# esc.net
KiCad netlist of a schematic drawn in EasyEDA Pro
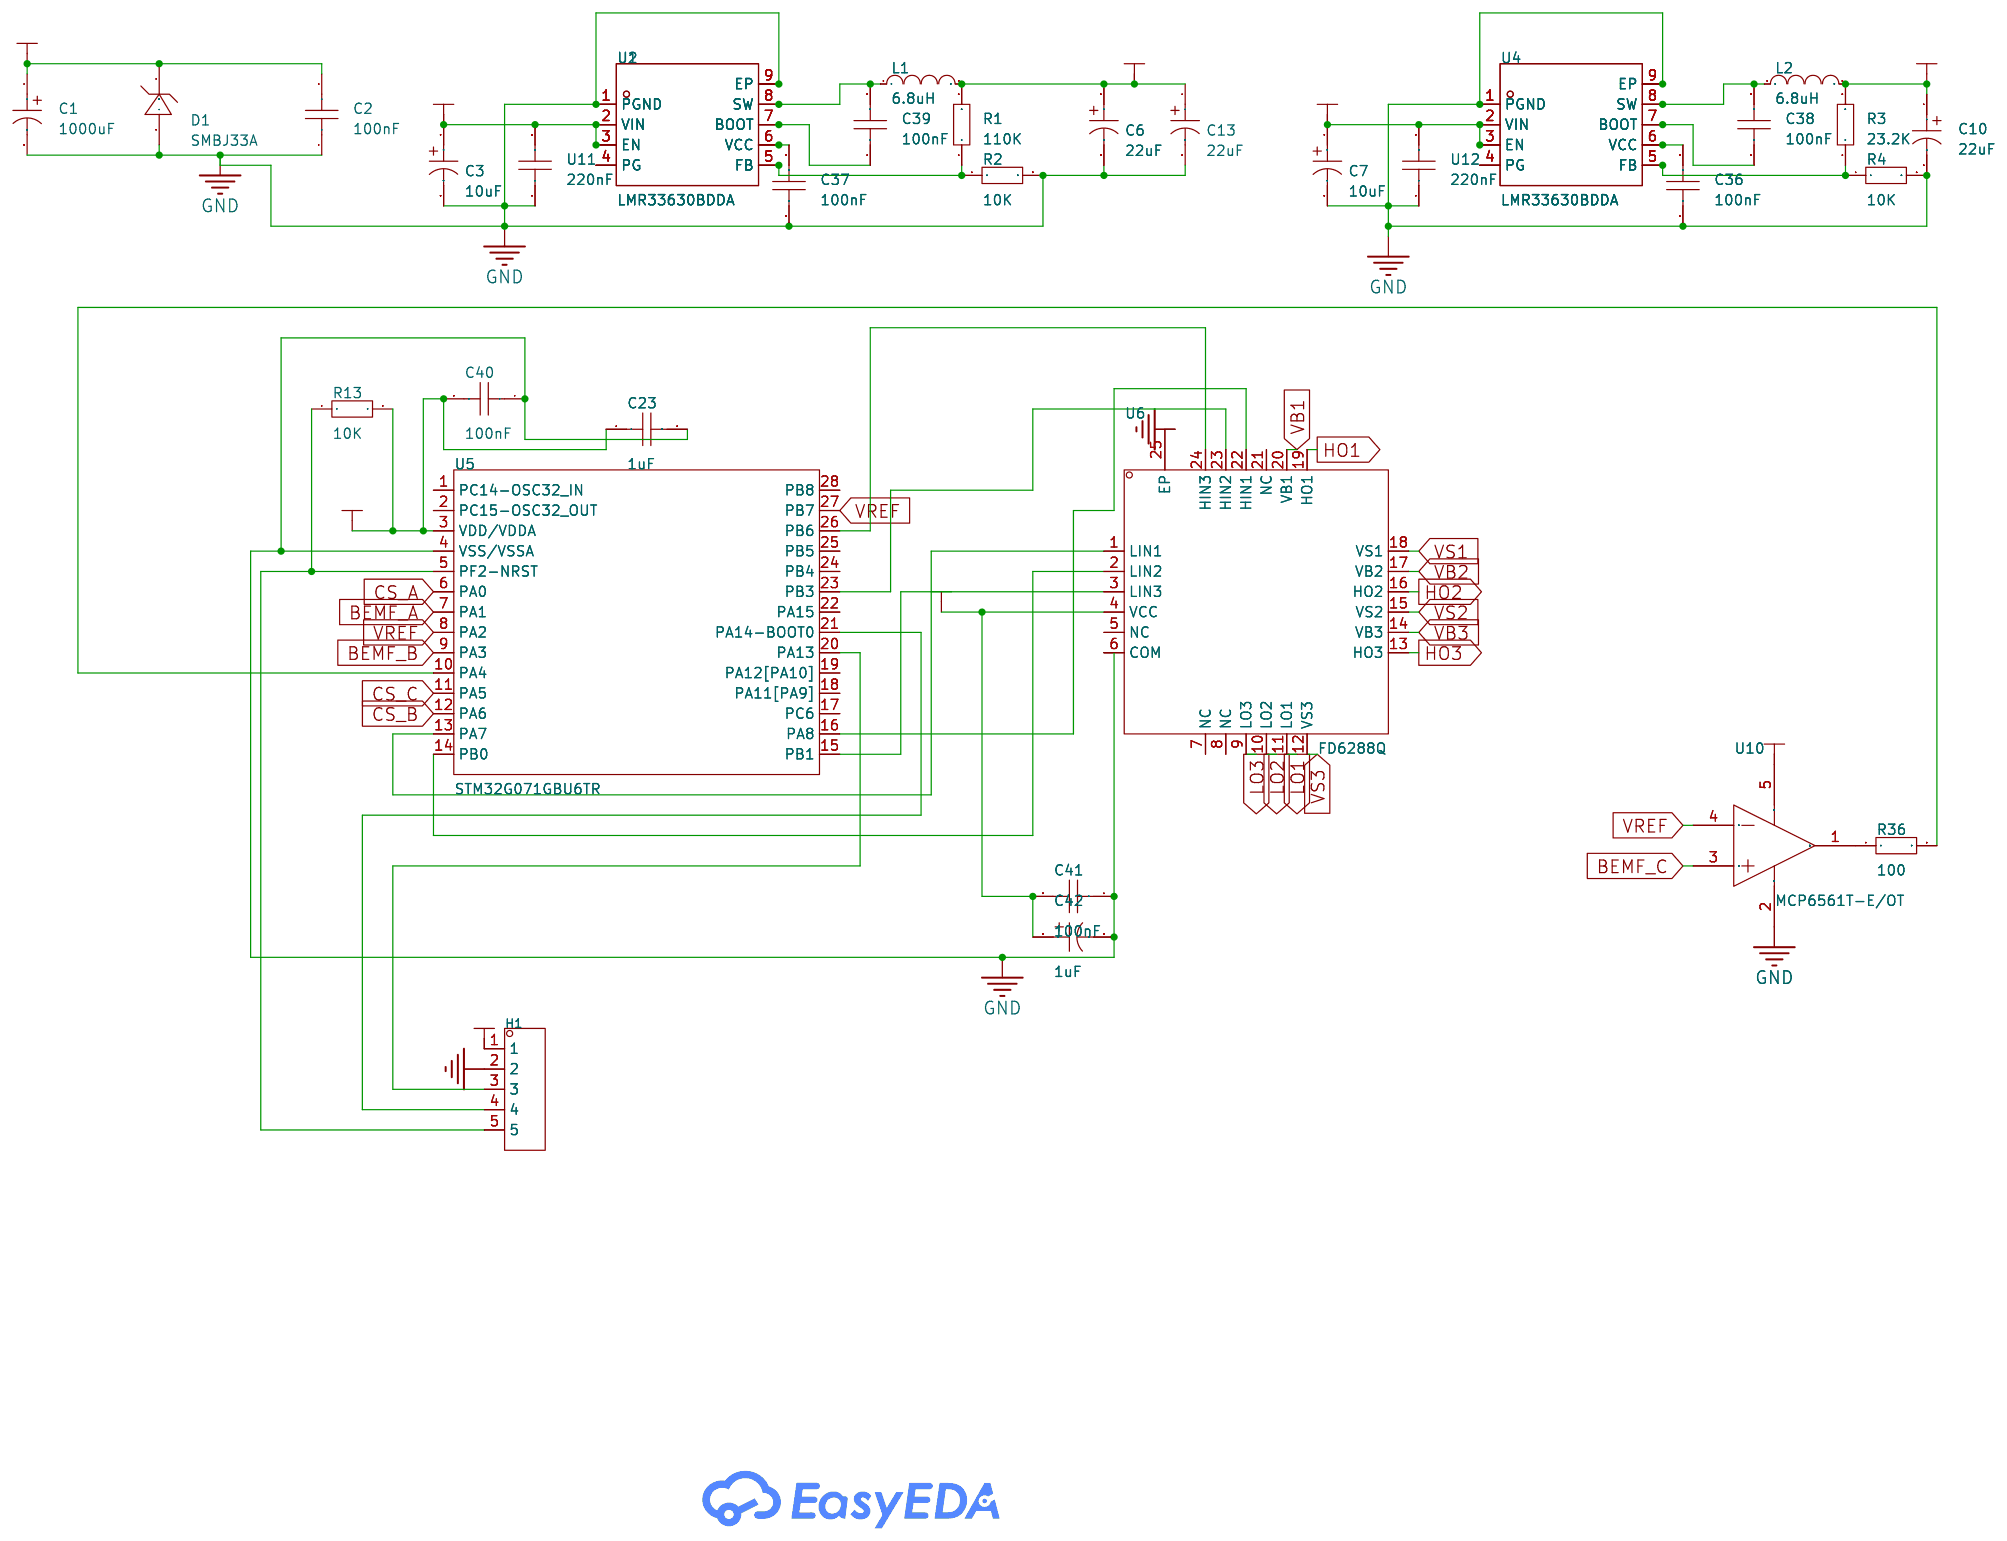
[diagram p0: P1]
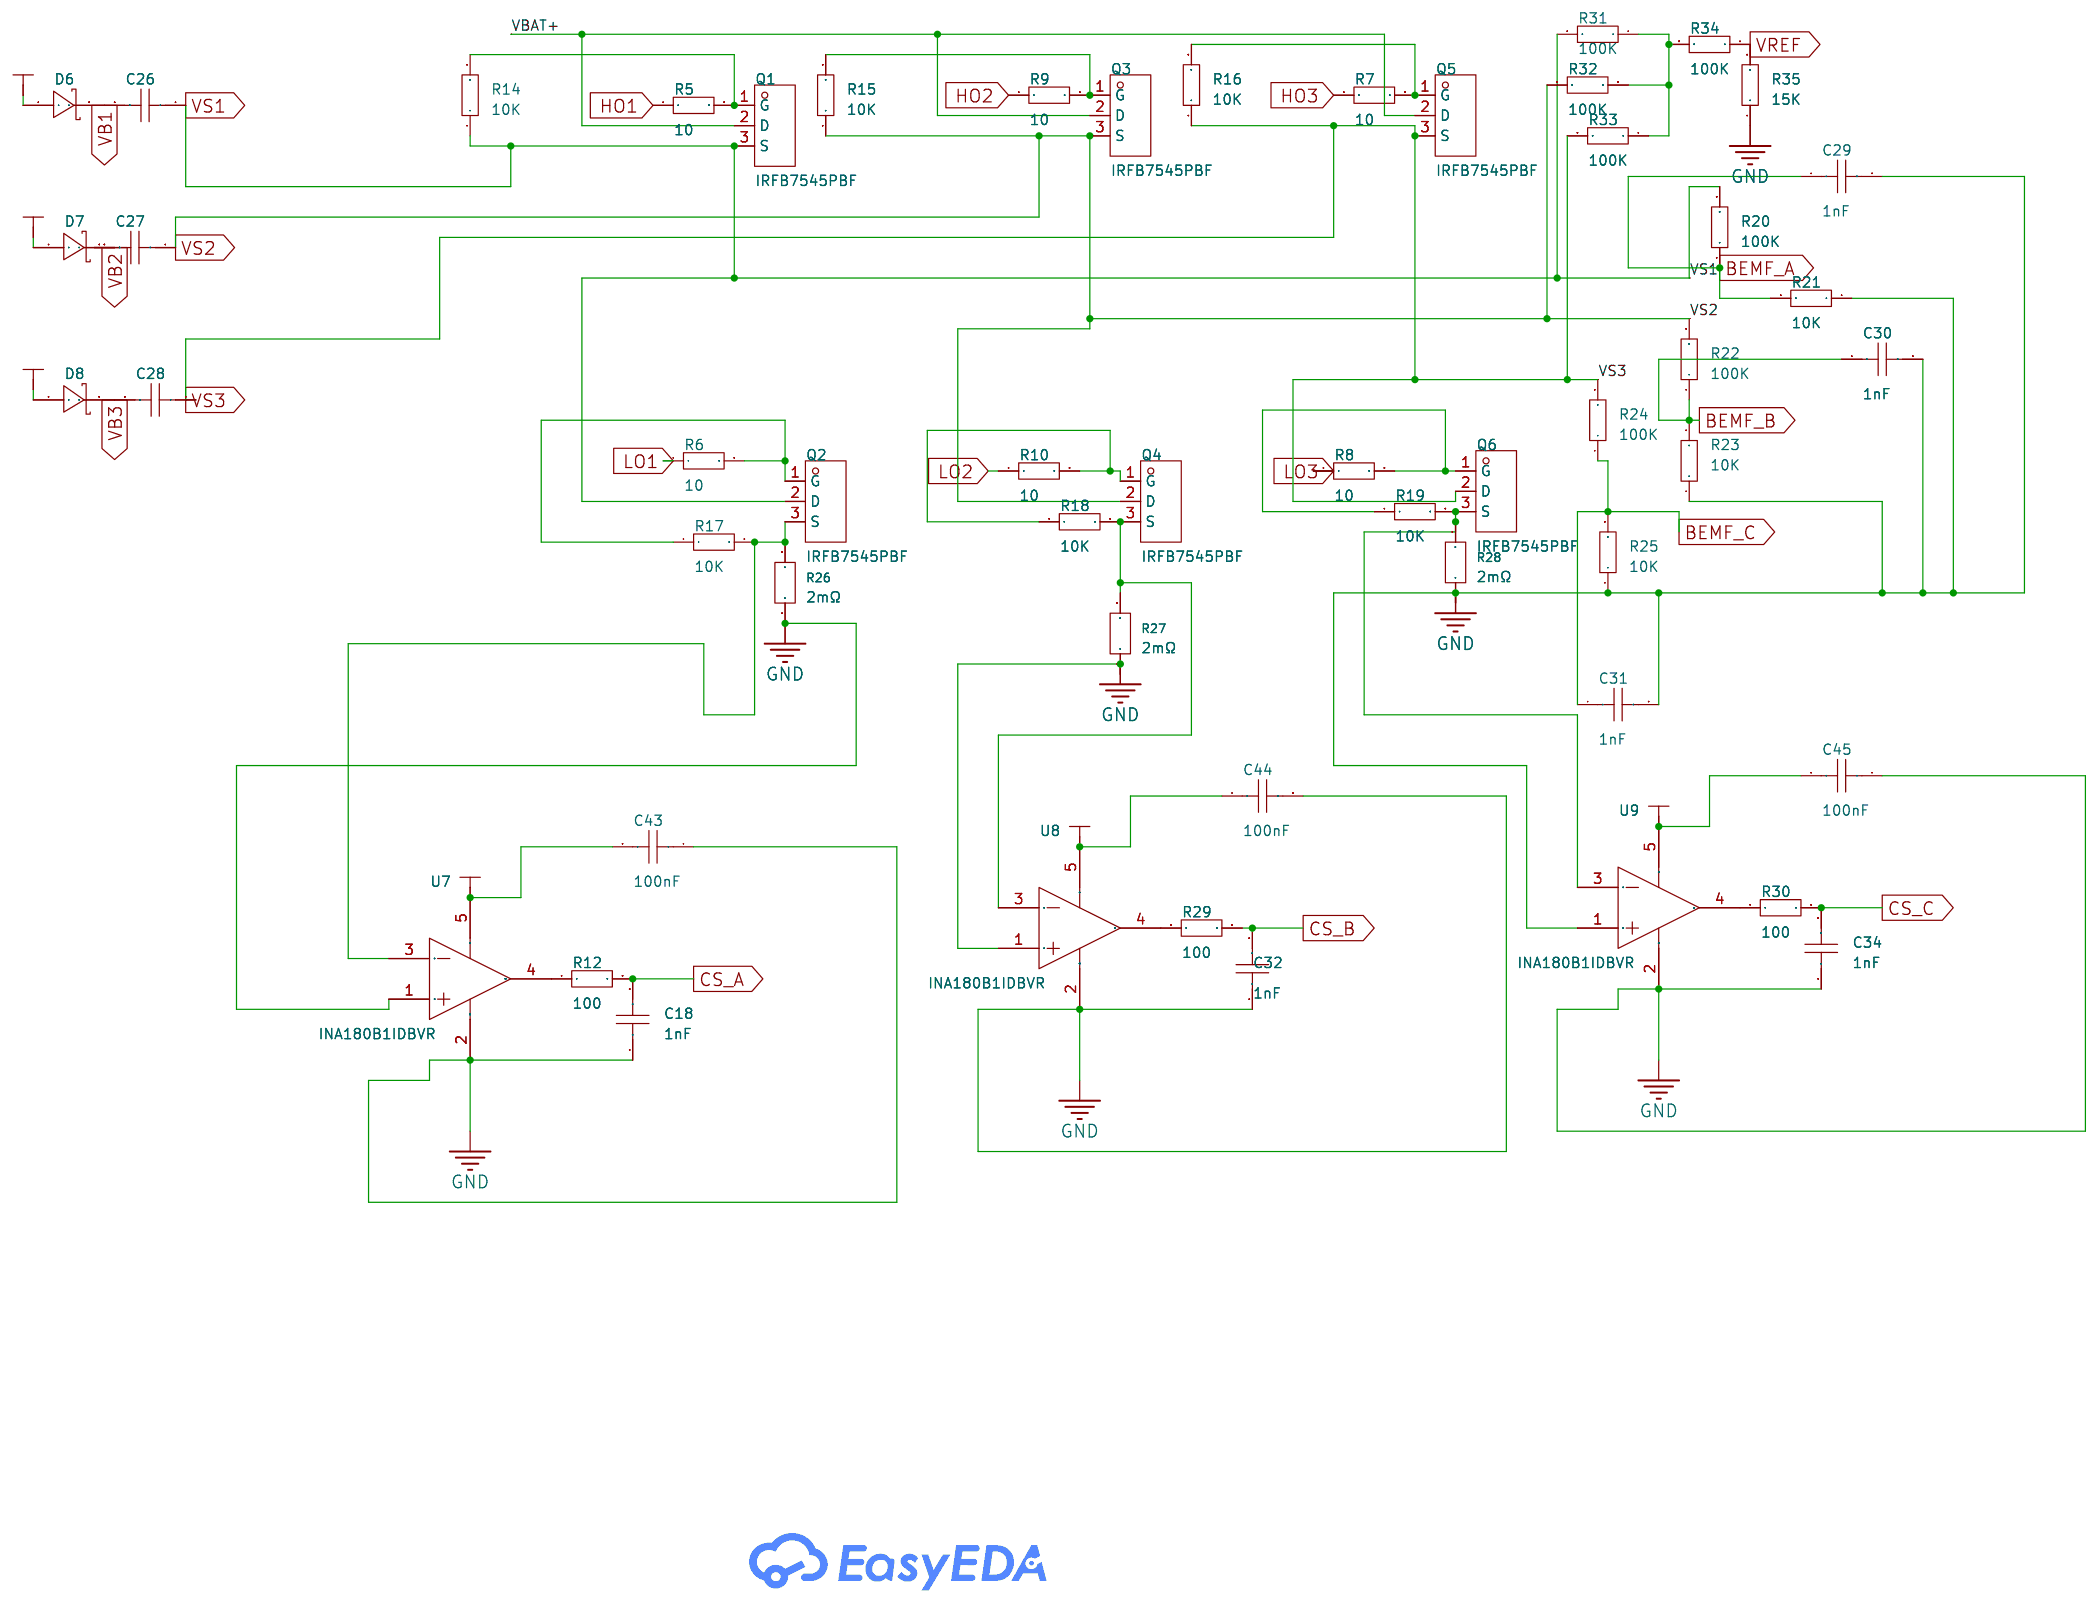
[diagram p1: P2]

(export (version "E")
  (design (tool "Eeschema 10.0.6"))
  (components
    (comp (ref "C1")
      (value "1000uF")
      (footprint "easyedapro:CAP-TH_BD13.0-P5.00-D0.6-FD")
      (fields (field (name "Manufacturer Part") "50V1000uF CD288") (field (name "Manufacturer") "HRK(鸿瑞凯电子)"))
      (libsource (lib "easyedapro") (part "50V1000UF CD288"))
    )
    (comp (ref "C2")
      (value "100nF")
      (footprint "easyedapro:C1111")
      (fields
        (field (name "Manufacturer Part") "200B104MT50XT1K")
        (field (name "Manufacturer") "Kyocera AVX")
      )
      (libsource (lib "easyedapro") (part "200B104MT50XT1K"))
    )
    (comp (ref "C3")
      (value "10uF")
      (footprint "easyedapro:CAP-TH_BD5.0-P2.00-D0.5-FD-1")
      (fields (field (name "Manufacturer Part") "50V10uF CD110") (field (name "Manufacturer") "HRK(鸿瑞凯电子)"))
      (libsource (lib "easyedapro") (part "50V10UF CD110_C2960373"))
    )
    (comp (ref "C6")
      (value "22uF")
      (footprint "easyedapro:CAP-TH_BD5.0-P2.00-D0.5-FD-1")
      (fields (field (name "Manufacturer Part") "22UF50VC110GF") (field (name "Manufacturer") "Econd(米朗电子)"))
      (libsource (lib "easyedapro") (part "22UF50VC110GF"))
    )
    (comp (ref "C7")
      (value "10uF")
      (footprint "easyedapro:CAP-TH_BD5.0-P2.00-D0.5-FD-1")
      (fields (field (name "Manufacturer Part") "50V10uF CD110") (field (name "Manufacturer") "HRK(鸿瑞凯电子)"))
      (libsource (lib "easyedapro") (part "50V10UF CD110_C2960373"))
    )
    (comp (ref "C10")
      (value "22uF")
      (footprint "easyedapro:CAP-TH_BD5.0-P2.00-D0.5-FD-1")
      (fields (field (name "Manufacturer Part") "22UF50VC110GF") (field (name "Manufacturer") "Econd(米朗电子)"))
      (libsource (lib "easyedapro") (part "22UF50VC110GF"))
    )
    (comp (ref "C13")
      (value "22uF")
      (footprint "easyedapro:CAP-TH_BD5.0-P2.00-D0.5-FD-1")
      (fields (field (name "Manufacturer Part") "22UF50VC110GF") (field (name "Manufacturer") "Econd(米朗电子)"))
      (libsource (lib "easyedapro") (part "22UF50VC110GF"))
    )
    (comp (ref "C23")
      (value "1uF")
      (footprint "easyedapro:C0603")
      (libsource (lib "easyedapro") (part "CapAcitance"))
    )
    (comp (ref "C36")
      (value "100nF")
      (footprint "easyedapro:C0603")
      (description "Capacitance:100nF Voltage Rating:50V Temperature Coefficient:X7R")
      (fields
        (field (name "Manufacturer Part") "CS1608X7R104K500NRB")
        (field (name "Manufacturer") "SAMWHA(三和)")
      )
      (libsource (lib "easyedapro") (part "CS1608X7R104K500NRB"))
    )
    (comp (ref "C37")
      (value "100nF")
      (footprint "easyedapro:C0603")
      (description "Capacitance:100nF Voltage Rating:50V Temperature Coefficient:X7R")
      (fields
        (field (name "Manufacturer Part") "CS1608X7R104K500NRB")
        (field (name "Manufacturer") "SAMWHA(三和)")
      )
      (libsource (lib "easyedapro") (part "CS1608X7R104K500NRB"))
    )
    (comp (ref "C38")
      (value "100nF")
      (footprint "easyedapro:C0603")
      (description "Capacitance:100nF Voltage Rating:50V Temperature Coefficient:X7R")
      (fields
        (field (name "Manufacturer Part") "CS1608X7R104K500NRB")
        (field (name "Manufacturer") "SAMWHA(三和)")
      )
      (libsource (lib "easyedapro") (part "CS1608X7R104K500NRB"))
    )
    (comp (ref "C39")
      (value "100nF")
      (footprint "easyedapro:C0603")
      (description "Capacitance:100nF Voltage Rating:50V Temperature Coefficient:X7R")
      (fields
        (field (name "Manufacturer Part") "CS1608X7R104K500NRB")
        (field (name "Manufacturer") "SAMWHA(三和)")
      )
      (libsource (lib "easyedapro") (part "CS1608X7R104K500NRB"))
    )
    (comp (ref "C40")
      (value "100nF")
      (footprint "easyedapro:C0603")
      (description "Capacitance:100nF Voltage Rating:50V Temperature Coefficient:X7R")
      (fields
        (field (name "Manufacturer Part") "CS1608X7R104K500NRB")
        (field (name "Manufacturer") "SAMWHA(三和)")
      )
      (libsource (lib "easyedapro") (part "CS1608X7R104K500NRB"))
    )
    (comp (ref "C41")
      (value "100nF")
      (footprint "easyedapro:C0603")
      (description "Capacitance:100nF Voltage Rating:50V Temperature Coefficient:X7R")
      (fields
        (field (name "Manufacturer Part") "CS1608X7R104K500NRB")
        (field (name "Manufacturer") "SAMWHA(三和)")
      )
      (libsource (lib "easyedapro") (part "CS1608X7R104K500NRB"))
    )
    (comp (ref "C42")
      (value "1uF")
      (footprint "easyedapro:CAP-TH_BD5.0-P2.00-D0.5-FD_1UF50V5X11GF")
      (fields (field (name "Manufacturer Part") "1uF50V5x11GF") (field (name "Manufacturer") "Econd(米朗电子)"))
      (libsource (lib "easyedapro") (part "1UF50V5X11GF"))
    )
    (comp (ref "D1")
      (value "SMBJ33A")
      (footprint "easyedapro:SMB_L4.6-W3.7-LS5.4-RD")
      (fields (field (name "Manufacturer") "PDW(芯格诺科技)"))
      (libsource (lib "easyedapro") (part "SMBJ33A_C49242950"))
    )
    (comp (ref "H1")
      (value "~")
      (footprint "easyedapro:HDR-TH_5P-P2.54-V-M")
      (libsource (lib "easyedapro") (part "MTP125-1105S1"))
    )
    (comp (ref "L1")
      (value "6.8uH")
      (footprint "easyedapro:L0603")
      (libsource (lib "easyedapro") (part "电感"))
    )
    (comp (ref "L2")
      (value "6.8uH")
      (footprint "easyedapro:L0603")
      (libsource (lib "easyedapro") (part "电感"))
    )
    (comp (ref "R1")
      (value "110K")
      (footprint "easyedapro:R0603")
      (libsource (lib "easyedapro") (part "Res"))
    )
    (comp (ref "R2") (value "10K") (footprint "easyedapro:R0603") (libsource (lib "easyedapro") (part "Res")))
    (comp (ref "R3")
      (value "23.2K")
      (footprint "easyedapro:R0603")
      (libsource (lib "easyedapro") (part "Res"))
    )
    (comp (ref "R4") (value "10K") (footprint "easyedapro:R0603") (libsource (lib "easyedapro") (part "Res")))
    (comp (ref "R13") (value "10K") (footprint "easyedapro:R0603") (libsource (lib "easyedapro") (part "电阻")))
    (comp (ref "R36")
      (value "100")
      (footprint "easyedapro:R0603")
      (libsource (lib "easyedapro") (part "Res"))
    )
    (comp (ref "U1")
      (value "LMR33630BDDA")
      (footprint "easyedapro:POWERPAD-SO-8_L4.9-W3.9-P1.27-LS6.0-BL-EP")
      (fields (field (name "Manufacturer") "TI(德州仪器)"))
      (libsource (lib "easyedapro") (part "LMR33630BDDA"))
    )
    (comp (ref "U2")
      (value "LMR33630BDDA")
      (footprint "easyedapro:POWERPAD-SO-8_L4.9-W3.9-P1.27-LS6.0-BL-EP")
      (fields (field (name "Manufacturer") "TI(德州仪器)"))
      (libsource (lib "easyedapro") (part "LMR33630BDDA"))
    )
    (comp (ref "U3")
      (value "LMR33630BDDA")
      (footprint "easyedapro:POWERPAD-SO-8_L4.9-W3.9-P1.27-LS6.0-BL-EP")
      (fields (field (name "Manufacturer") "TI(德州仪器)"))
      (libsource (lib "easyedapro") (part "LMR33630BDDA"))
    )
    (comp (ref "U4")
      (value "LMR33630BDDA")
      (footprint "easyedapro:POWERPAD-SO-8_L4.9-W3.9-P1.27-LS6.0-BL-EP")
      (fields (field (name "Manufacturer") "TI(德州仪器)"))
      (libsource (lib "easyedapro") (part "LMR33630BDDA"))
    )
    (comp (ref "U5")
      (value "STM32G071GBU6TR")
      (footprint "easyedapro:UFQFPN-28_L4.0-W4.0-P0.50-BL")
      (fields (field (name "Manufacturer") "ST(意法半导体)"))
      (libsource (lib "easyedapro") (part "STM32G071GBU6TR"))
    )
    (comp (ref "U6")
      (value "FD6288Q")
      (footprint "easyedapro:QFN-24_L4.0-W4.0-P0.50-BL-EP2.6")
      (fields (field (name "Manufacturer") "Fortior Tech(峰岹)"))
      (libsource (lib "easyedapro") (part "FD6288Q_C328453"))
    )
    (comp (ref "U10")
      (value "MCP6561T-E/OT")
      (footprint "easyedapro:SOT-23-5_L3.0-W1.7-P0.95-LS2.8-BR")
      (fields (field (name "Manufacturer") "MICROCHIP(美国微芯)"))
      (libsource (lib "easyedapro") (part "MCP6561T-E/OT"))
    )
    (comp (ref "U11")
      (value "220nF")
      (footprint "easyedapro:CAP-TH_L4.0-W2.5-P2.50-D0.5")
      (description "Capacitance:220nF Tolerance:±10% Tolerance:±10% Voltage Rating:50V Temperature Coefficient:X7R")
      (fields (field (name "Manufacturer Part") "FK18X7R1H224K") (field (name "Manufacturer") "TDK"))
      (libsource (lib "easyedapro") (part "FK18X7R1H224K"))
    )
    (comp (ref "U12")
      (value "220nF")
      (footprint "easyedapro:CAP-TH_L4.0-W2.5-P2.50-D0.5")
      (description "Capacitance:220nF Tolerance:±10% Tolerance:±10% Voltage Rating:50V Temperature Coefficient:X7R")
      (fields (field (name "Manufacturer Part") "FK18X7R1H224K") (field (name "Manufacturer") "TDK"))
      (libsource (lib "easyedapro") (part "FK18X7R1H224K"))
    )
    (comp (ref "C18")
      (value "1nF")
      (footprint "easyedapro:C0603")
      (libsource (lib "easyedapro") (part "CAP"))
    )
    (comp (ref "C26")
      (value "220nF")
      (footprint "easyedapro:C0805")
      (fields
        (field (name "Manufacturer Part") "TCC0805X7R224K500DT")
        (field (name "Manufacturer") "CCTC(三环)")
      )
      (libsource (lib "easyedapro") (part "TCC0805X7R224K500DT"))
    )
    (comp (ref "C27")
      (value "220nF")
      (footprint "easyedapro:C0805")
      (fields
        (field (name "Manufacturer Part") "TCC0805X7R224K500DT")
        (field (name "Manufacturer") "CCTC(三环)")
      )
      (libsource (lib "easyedapro") (part "TCC0805X7R224K500DT"))
    )
    (comp (ref "C28")
      (value "220nF")
      (footprint "easyedapro:C0805")
      (fields
        (field (name "Manufacturer Part") "TCC0805X7R224K500DT")
        (field (name "Manufacturer") "CCTC(三环)")
      )
      (libsource (lib "easyedapro") (part "TCC0805X7R224K500DT"))
    )
    (comp (ref "C29")
      (value "1nF")
      (footprint "easyedapro:C0603")
      (libsource (lib "easyedapro") (part "CapAcitance"))
    )
    (comp (ref "C30")
      (value "1nF")
      (footprint "easyedapro:C0603")
      (libsource (lib "easyedapro") (part "CapAcitance"))
    )
    (comp (ref "C31")
      (value "1nF")
      (footprint "easyedapro:C0603")
      (libsource (lib "easyedapro") (part "CapAcitance"))
    )
    (comp (ref "C32")
      (value "1nF")
      (footprint "easyedapro:C0603")
      (libsource (lib "easyedapro") (part "CAP"))
    )
    (comp (ref "C34")
      (value "1nF")
      (footprint "easyedapro:C0603")
      (libsource (lib "easyedapro") (part "CAP"))
    )
    (comp (ref "C43")
      (value "100nF")
      (footprint "easyedapro:C0603")
      (description "Capacitance:100nF Voltage Rating:50V Temperature Coefficient:X7R")
      (fields
        (field (name "Manufacturer Part") "CS1608X7R104K500NRB")
        (field (name "Manufacturer") "SAMWHA(三和)")
      )
      (libsource (lib "easyedapro") (part "CS1608X7R104K500NRB"))
    )
    (comp (ref "C44")
      (value "100nF")
      (footprint "easyedapro:C0603")
      (description "Capacitance:100nF Voltage Rating:50V Temperature Coefficient:X7R")
      (fields
        (field (name "Manufacturer Part") "CS1608X7R104K500NRB")
        (field (name "Manufacturer") "SAMWHA(三和)")
      )
      (libsource (lib "easyedapro") (part "CS1608X7R104K500NRB"))
    )
    (comp (ref "C45")
      (value "100nF")
      (footprint "easyedapro:C0603")
      (description "Capacitance:100nF Voltage Rating:50V Temperature Coefficient:X7R")
      (fields
        (field (name "Manufacturer Part") "CS1608X7R104K500NRB")
        (field (name "Manufacturer") "SAMWHA(三和)")
      )
      (libsource (lib "easyedapro") (part "CS1608X7R104K500NRB"))
    )
    (comp (ref "D6")
      (value "~")
      (footprint "easyedapro:SMA_L4.4-W2.8-LS5.4-R-RD")
      (description "Reverse Voltage (Vr):40V Average Rectified Current (Io):5A Forward Voltage (Vf@If):550mV@5A")
      (fields (field (name "Manufacturer Part") "SS54") (field (name "Manufacturer") "MDD"))
      (libsource (lib "easyedapro") (part "SS54_C22452"))
    )
    (comp (ref "D7")
      (value "~")
      (footprint "easyedapro:SMA_L4.4-W2.8-LS5.4-R-RD")
      (description "Reverse Voltage (Vr):40V Average Rectified Current (Io):5A Forward Voltage (Vf@If):550mV@5A")
      (fields (field (name "Manufacturer Part") "SS54") (field (name "Manufacturer") "MDD"))
      (libsource (lib "easyedapro") (part "SS54_C22452"))
    )
    (comp (ref "D8")
      (value "~")
      (footprint "easyedapro:SMA_L4.4-W2.8-LS5.4-R-RD")
      (description "Reverse Voltage (Vr):40V Average Rectified Current (Io):5A Forward Voltage (Vf@If):550mV@5A")
      (fields (field (name "Manufacturer Part") "SS54") (field (name "Manufacturer") "MDD"))
      (libsource (lib "easyedapro") (part "SS54_C22452"))
    )
    (comp (ref "Q1")
      (value "IRFB7545PBF")
      (footprint "easyedapro:TO-220-3_L10.0-W4.5-P2.54-L")
      (fields (field (name "Manufacturer") "Infineon(英飞凌)"))
      (libsource (lib "easyedapro") (part "IRFB7545PBF"))
    )
    (comp (ref "Q2")
      (value "IRFB7545PBF")
      (footprint "easyedapro:TO-220-3_L10.0-W4.5-P2.54-L")
      (fields (field (name "Manufacturer") "Infineon(英飞凌)"))
      (libsource (lib "easyedapro") (part "IRFB7545PBF"))
    )
    (comp (ref "Q3")
      (value "IRFB7545PBF")
      (footprint "easyedapro:TO-220-3_L10.0-W4.5-P2.54-L")
      (fields (field (name "Manufacturer") "Infineon(英飞凌)"))
      (libsource (lib "easyedapro") (part "IRFB7545PBF"))
    )
    (comp (ref "Q4")
      (value "IRFB7545PBF")
      (footprint "easyedapro:TO-220-3_L10.0-W4.5-P2.54-L")
      (fields (field (name "Manufacturer") "Infineon(英飞凌)"))
      (libsource (lib "easyedapro") (part "IRFB7545PBF"))
    )
    (comp (ref "Q5")
      (value "IRFB7545PBF")
      (footprint "easyedapro:TO-220-3_L10.0-W4.5-P2.54-L")
      (fields (field (name "Manufacturer") "Infineon(英飞凌)"))
      (libsource (lib "easyedapro") (part "IRFB7545PBF"))
    )
    (comp (ref "Q6")
      (value "IRFB7545PBF")
      (footprint "easyedapro:TO-220-3_L10.0-W4.5-P2.54-L")
      (fields (field (name "Manufacturer") "Infineon(英飞凌)"))
      (libsource (lib "easyedapro") (part "IRFB7545PBF"))
    )
    (comp (ref "R5") (value "10") (footprint "easyedapro:R0603") (libsource (lib "easyedapro") (part "Res")))
    (comp (ref "R6") (value "10") (footprint "easyedapro:R0603") (libsource (lib "easyedapro") (part "Res")))
    (comp (ref "R7") (value "10") (footprint "easyedapro:R0603") (libsource (lib "easyedapro") (part "Res")))
    (comp (ref "R8") (value "10") (footprint "easyedapro:R0603") (libsource (lib "easyedapro") (part "Res")))
    (comp (ref "R9") (value "10") (footprint "easyedapro:R0603") (libsource (lib "easyedapro") (part "Res")))
    (comp (ref "R10") (value "10") (footprint "easyedapro:R0603") (libsource (lib "easyedapro") (part "Res")))
    (comp (ref "R12")
      (value "100")
      (footprint "easyedapro:R0603")
      (libsource (lib "easyedapro") (part "Res"))
    )
    (comp (ref "R14") (value "10K") (footprint "easyedapro:R0603") (libsource (lib "easyedapro") (part "电阻")))
    (comp (ref "R15") (value "10K") (footprint "easyedapro:R0603") (libsource (lib "easyedapro") (part "电阻")))
    (comp (ref "R16") (value "10K") (footprint "easyedapro:R0603") (libsource (lib "easyedapro") (part "电阻")))
    (comp (ref "R17") (value "10K") (footprint "easyedapro:R0603") (libsource (lib "easyedapro") (part "电阻")))
    (comp (ref "R18") (value "10K") (footprint "easyedapro:R0603") (libsource (lib "easyedapro") (part "电阻")))
    (comp (ref "R19") (value "10K") (footprint "easyedapro:R0603") (libsource (lib "easyedapro") (part "电阻")))
    (comp (ref "R20")
      (value "100K")
      (footprint "easyedapro:R0603")
      (libsource (lib "easyedapro") (part "电阻"))
    )
    (comp (ref "R21") (value "10K") (footprint "easyedapro:R0603") (libsource (lib "easyedapro") (part "电阻")))
    (comp (ref "R22")
      (value "100K")
      (footprint "easyedapro:R0603")
      (libsource (lib "easyedapro") (part "电阻"))
    )
    (comp (ref "R23") (value "10K") (footprint "easyedapro:R0603") (libsource (lib "easyedapro") (part "电阻")))
    (comp (ref "R24")
      (value "100K")
      (footprint "easyedapro:R0603")
      (libsource (lib "easyedapro") (part "电阻"))
    )
    (comp (ref "R25") (value "10K") (footprint "easyedapro:R0603") (libsource (lib "easyedapro") (part "电阻")))
    (comp (ref "R26")
      (value "2mΩ")
      (footprint "easyedapro:R5930")
      (fields
        (field (name "Manufacturer Part") "HolRS5930-5W-2mR-1%")
        (field (name "Manufacturer") "Milliohm(毫欧)")
      )
      (libsource (lib "easyedapro") (part "HOLRS5930-5W-2MR-1%"))
    )
    (comp (ref "R27")
      (value "2mΩ")
      (footprint "easyedapro:R5930")
      (fields
        (field (name "Manufacturer Part") "HolRS5930-5W-2mR-1%")
        (field (name "Manufacturer") "Milliohm(毫欧)")
      )
      (libsource (lib "easyedapro") (part "HOLRS5930-5W-2MR-1%"))
    )
    (comp (ref "R28")
      (value "2mΩ")
      (footprint "easyedapro:R5930")
      (fields
        (field (name "Manufacturer Part") "HolRS5930-5W-2mR-1%")
        (field (name "Manufacturer") "Milliohm(毫欧)")
      )
      (libsource (lib "easyedapro") (part "HOLRS5930-5W-2MR-1%"))
    )
    (comp (ref "R29")
      (value "100")
      (footprint "easyedapro:R0603")
      (libsource (lib "easyedapro") (part "Res"))
    )
    (comp (ref "R30")
      (value "100")
      (footprint "easyedapro:R0603")
      (libsource (lib "easyedapro") (part "Res"))
    )
    (comp (ref "R31")
      (value "100K")
      (footprint "easyedapro:R0603")
      (libsource (lib "easyedapro") (part "电阻"))
    )
    (comp (ref "R32")
      (value "100K")
      (footprint "easyedapro:R0603")
      (libsource (lib "easyedapro") (part "电阻"))
    )
    (comp (ref "R33")
      (value "100K")
      (footprint "easyedapro:R0603")
      (libsource (lib "easyedapro") (part "电阻"))
    )
    (comp (ref "R34")
      (value "100K")
      (footprint "easyedapro:R0603")
      (libsource (lib "easyedapro") (part "电阻"))
    )
    (comp (ref "R35") (value "15K") (footprint "easyedapro:R0603") (libsource (lib "easyedapro") (part "电阻")))
    (comp (ref "U7")
      (value "INA180B1IDBVR")
      (footprint "easyedapro:SOT-23-5_L2.9-W1.6-P0.95-LS2.8-BR")
      (fields (field (name "Manufacturer") "TI(德州仪器)"))
      (libsource (lib "easyedapro") (part "INA180B1IDBVR"))
    )
    (comp (ref "U8")
      (value "INA180B1IDBVR")
      (footprint "easyedapro:SOT-23-5_L2.9-W1.6-P0.95-LS2.8-BR")
      (fields (field (name "Manufacturer") "TI(德州仪器)"))
      (libsource (lib "easyedapro") (part "INA180B1IDBVR"))
    )
    (comp (ref "U9")
      (value "INA180B1IDBVR")
      (footprint "easyedapro:SOT-23-5_L2.9-W1.6-P0.95-LS2.8-BR")
      (fields (field (name "Manufacturer") "TI(德州仪器)"))
      (libsource (lib "easyedapro") (part "INA180B1IDBVR"))
    )
  )
  (nets
    (net (code "1") (name "+3.3V") (class "Default")
      (node (ref "C10") (pin "1") (pinfunction "1_1") (pintype "input"))
      (node (ref "C23") (pin "1") (pinfunction "1_1") (pintype "input"))
      (node (ref "C40") (pin "2") (pinfunction "2_2") (pintype "unspecified"))
      (node (ref "C43") (pin "2") (pinfunction "2_2") (pintype "unspecified"))
      (node (ref "C44") (pin "1") (pinfunction "1_1") (pintype "unspecified"))
      (node (ref "C45") (pin "2") (pinfunction "2_2") (pintype "unspecified"))
      (node (ref "H1") (pin "1") (pinfunction "1_1") (pintype "input"))
      (node (ref "L2") (pin "2") (pinfunction "2_2") (pintype "input"))
      (node (ref "R13") (pin "2") (pinfunction "2_2") (pintype "input"))
      (node (ref "R3") (pin "2") (pinfunction "2_2") (pintype "input"))
      (node (ref "U10") (pin "5") (pinfunction "VDD_5") (pintype "input"))
      (node (ref "U5") (pin "3") (pinfunction "VDD/VDDA_3") (pintype "unspecified"))
      (node (ref "U7") (pin "5") (pinfunction "VS_5") (pintype "input"))
      (node (ref "U8") (pin "5") (pinfunction "VS_5") (pintype "input"))
      (node (ref "U9") (pin "5") (pinfunction "VS_5") (pintype "input"))
    )
    (net (code "2") (name "+12V") (class "Default")
      (node (ref "C13") (pin "1") (pinfunction "1_1") (pintype "input"))
      (node (ref "C41") (pin "2") (pinfunction "2_2") (pintype "unspecified"))
      (node (ref "C42") (pin "1") (pinfunction "1_1") (pintype "input"))
      (node (ref "C6") (pin "1") (pinfunction "1_1") (pintype "input"))
      (node (ref "C7") (pin "1") (pinfunction "1_1") (pintype "input"))
      (node (ref "D6") (pin "1") (pinfunction "A_1") (pintype "input"))
      (node (ref "D7") (pin "1") (pinfunction "A_1") (pintype "input"))
      (node (ref "D8") (pin "1") (pinfunction "A_1") (pintype "input"))
      (node (ref "L1") (pin "2") (pinfunction "2_2") (pintype "input"))
      (node (ref "R1") (pin "2") (pinfunction "2_2") (pintype "input"))
      (node (ref "U12") (pin "2") (pinfunction "2_2") (pintype "unspecified"))
      (node (ref "U3") (pin "2") (pinfunction "VIN_2") (pintype "unspecified"))
      (node (ref "U3") (pin "3") (pinfunction "EN_3") (pintype "unspecified"))
      (node (ref "U4") (pin "2") (pinfunction "VIN_2") (pintype "unspecified"))
      (node (ref "U4") (pin "3") (pinfunction "EN_3") (pintype "unspecified"))
      (node (ref "U6") (pin "4") (pinfunction "VCC_4") (pintype "unspecified"))
    )
    (net (code "3") (name "+25.2V") (class "Default")
      (node (ref "C1") (pin "1") (pinfunction "1_1") (pintype "input"))
      (node (ref "C2") (pin "2") (pinfunction "2_2") (pintype "unspecified"))
      (node (ref "C3") (pin "1") (pinfunction "1_1") (pintype "input"))
      (node (ref "D1") (pin "1") (pinfunction "C_1") (pintype "unspecified"))
      (node (ref "U1") (pin "2") (pinfunction "VIN_2") (pintype "unspecified"))
      (node (ref "U1") (pin "3") (pinfunction "EN_3") (pintype "unspecified"))
      (node (ref "U11") (pin "2") (pinfunction "2_2") (pintype "unspecified"))
      (node (ref "U2") (pin "2") (pinfunction "VIN_2") (pintype "unspecified"))
      (node (ref "U2") (pin "3") (pinfunction "EN_3") (pintype "unspecified"))
    )
    (net (code "4") (name "BEMF_A") (class "Default")
      (node (ref "C29") (pin "1") (pinfunction "1_1") (pintype "input"))
      (node (ref "R20") (pin "1") (pinfunction "1_1") (pintype "input"))
      (node (ref "R21") (pin "2") (pinfunction "2_2") (pintype "input"))
      (node (ref "U5") (pin "7") (pinfunction "PA1_7") (pintype "unspecified"))
    )
    (net (code "5") (name "BEMF_B") (class "Default")
      (node (ref "C30") (pin "1") (pinfunction "1_1") (pintype "input"))
      (node (ref "R22") (pin "1") (pinfunction "1_1") (pintype "input"))
      (node (ref "R23") (pin "2") (pinfunction "2_2") (pintype "input"))
      (node (ref "U5") (pin "9") (pinfunction "PA3_9") (pintype "unspecified"))
    )
    (net (code "6") (name "BEMF_C") (class "Default")
      (node (ref "C31") (pin "1") (pinfunction "1_1") (pintype "input"))
      (node (ref "R24") (pin "1") (pinfunction "1_1") (pintype "input"))
      (node (ref "R25") (pin "2") (pinfunction "2_2") (pintype "input"))
      (node (ref "U10") (pin "3") (pinfunction "IN+_3") (pintype "input"))
    )
    (net (code "7") (name "CS_A") (class "Default")
      (node (ref "C18") (pin "2") (pinfunction "2_2") (pintype "input"))
      (node (ref "R12") (pin "2") (pinfunction "2_2") (pintype "input"))
      (node (ref "U5") (pin "6") (pinfunction "PA0_6") (pintype "unspecified"))
    )
    (net (code "8") (name "CS_B") (class "Default")
      (node (ref "C32") (pin "2") (pinfunction "2_2") (pintype "input"))
      (node (ref "R29") (pin "2") (pinfunction "2_2") (pintype "input"))
      (node (ref "U5") (pin "12") (pinfunction "PA6_12") (pintype "unspecified"))
    )
    (net (code "9") (name "CS_C") (class "Default")
      (node (ref "C34") (pin "2") (pinfunction "2_2") (pintype "input"))
      (node (ref "R30") (pin "2") (pinfunction "2_2") (pintype "input"))
      (node (ref "U5") (pin "11") (pinfunction "PA5_11") (pintype "unspecified"))
    )
    (net (code "10") (name "GND") (class "Default")
      (node (ref "C1") (pin "2") (pinfunction "2_2") (pintype "input"))
      (node (ref "C10") (pin "2") (pinfunction "2_2") (pintype "input"))
      (node (ref "C13") (pin "2") (pinfunction "2_2") (pintype "input"))
      (node (ref "C18") (pin "1") (pinfunction "1_1") (pintype "input"))
      (node (ref "C2") (pin "1") (pinfunction "1_1") (pintype "unspecified"))
      (node (ref "C23") (pin "2") (pinfunction "2_2") (pintype "input"))
      (node (ref "C29") (pin "2") (pinfunction "2_2") (pintype "input"))
      (node (ref "C3") (pin "2") (pinfunction "2_2") (pintype "input"))
      (node (ref "C30") (pin "2") (pinfunction "2_2") (pintype "input"))
      (node (ref "C31") (pin "2") (pinfunction "2_2") (pintype "input"))
      (node (ref "C32") (pin "1") (pinfunction "1_1") (pintype "input"))
      (node (ref "C34") (pin "1") (pinfunction "1_1") (pintype "input"))
      (node (ref "C36") (pin "1") (pinfunction "1_1") (pintype "unspecified"))
      (node (ref "C37") (pin "1") (pinfunction "1_1") (pintype "unspecified"))
      (node (ref "C40") (pin "1") (pinfunction "1_1") (pintype "unspecified"))
      (node (ref "C41") (pin "1") (pinfunction "1_1") (pintype "unspecified"))
      (node (ref "C42") (pin "2") (pinfunction "2_2") (pintype "input"))
      (node (ref "C43") (pin "1") (pinfunction "1_1") (pintype "unspecified"))
      (node (ref "C44") (pin "2") (pinfunction "2_2") (pintype "unspecified"))
      (node (ref "C45") (pin "1") (pinfunction "1_1") (pintype "unspecified"))
      (node (ref "C6") (pin "2") (pinfunction "2_2") (pintype "input"))
      (node (ref "C7") (pin "2") (pinfunction "2_2") (pintype "input"))
      (node (ref "D1") (pin "2") (pinfunction "A_2") (pintype "unspecified"))
      (node (ref "H1") (pin "2") (pinfunction "2_2") (pintype "input"))
      (node (ref "R2") (pin "2") (pinfunction "2_2") (pintype "input"))
      (node (ref "R21") (pin "1") (pinfunction "1_1") (pintype "input"))
      (node (ref "R23") (pin "1") (pinfunction "1_1") (pintype "input"))
      (node (ref "R25") (pin "1") (pinfunction "1_1") (pintype "input"))
      (node (ref "R26") (pin "1") (pinfunction "1_1") (pintype "input"))
      (node (ref "R27") (pin "1") (pinfunction "1_1") (pintype "input"))
      (node (ref "R28") (pin "1") (pinfunction "1_1") (pintype "input"))
      (node (ref "R35") (pin "1") (pinfunction "1_1") (pintype "input"))
      (node (ref "R4") (pin "2") (pinfunction "2_2") (pintype "input"))
      (node (ref "U1") (pin "1") (pinfunction "PGND_1") (pintype "unspecified"))
      (node (ref "U1") (pin "9") (pinfunction "EP_9") (pintype "unspecified"))
      (node (ref "U10") (pin "2") (pinfunction "VSS_2") (pintype "input"))
      (node (ref "U11") (pin "1") (pinfunction "1_1") (pintype "unspecified"))
      (node (ref "U12") (pin "1") (pinfunction "1_1") (pintype "unspecified"))
      (node (ref "U2") (pin "1") (pinfunction "PGND_1") (pintype "unspecified"))
      (node (ref "U2") (pin "9") (pinfunction "EP_9") (pintype "unspecified"))
      (node (ref "U3") (pin "1") (pinfunction "PGND_1") (pintype "unspecified"))
      (node (ref "U3") (pin "9") (pinfunction "EP_9") (pintype "unspecified"))
      (node (ref "U4") (pin "1") (pinfunction "PGND_1") (pintype "unspecified"))
      (node (ref "U4") (pin "9") (pinfunction "EP_9") (pintype "unspecified"))
      (node (ref "U5") (pin "4") (pinfunction "VSS/VSSA_4") (pintype "unspecified"))
      (node (ref "U6") (pin "25") (pinfunction "EP_25") (pintype "unspecified"))
      (node (ref "U6") (pin "6") (pinfunction "COM_6") (pintype "unspecified"))
      (node (ref "U7") (pin "1") (pinfunction "IN+_1") (pintype "input"))
      (node (ref "U7") (pin "2") (pinfunction "GND_2") (pintype "input"))
      (node (ref "U8") (pin "1") (pinfunction "IN+_1") (pintype "input"))
      (node (ref "U8") (pin "2") (pinfunction "GND_2") (pintype "input"))
      (node (ref "U9") (pin "1") (pinfunction "IN+_1") (pintype "input"))
      (node (ref "U9") (pin "2") (pinfunction "GND_2") (pintype "input"))
    )
    (net (code "11") (name "HO1") (class "Default")
      (node (ref "R5") (pin "1") (pinfunction "1_1") (pintype "input"))
      (node (ref "U6") (pin "19") (pinfunction "HO1_19") (pintype "unspecified"))
    )
    (net (code "12") (name "HO2") (class "Default")
      (node (ref "R9") (pin "1") (pinfunction "1_1") (pintype "input"))
      (node (ref "U6") (pin "16") (pinfunction "HO2_16") (pintype "unspecified"))
    )
    (net (code "13") (name "HO3") (class "Default")
      (node (ref "R7") (pin "1") (pinfunction "1_1") (pintype "input"))
      (node (ref "U6") (pin "13") (pinfunction "HO3_13") (pintype "unspecified"))
    )
    (net (code "14") (name "LO1") (class "Default")
      (node (ref "R6") (pin "1") (pinfunction "1_1") (pintype "input"))
      (node (ref "U6") (pin "11") (pinfunction "LO1_11") (pintype "unspecified"))
    )
    (net (code "15") (name "LO2") (class "Default")
      (node (ref "R10") (pin "1") (pinfunction "1_1") (pintype "input"))
      (node (ref "U6") (pin "10") (pinfunction "LO2_10") (pintype "unspecified"))
    )
    (net (code "16") (name "LO3") (class "Default")
      (node (ref "R8") (pin "1") (pinfunction "1_1") (pintype "input"))
      (node (ref "U6") (pin "9") (pinfunction "LO3_9") (pintype "unspecified"))
    )
    (net (code "17") (name "Net-(Q1-G)") (class "Default")
      (node (ref "Q1") (pin "1") (pinfunction "G_1") (pintype "unspecified"))
      (node (ref "R14") (pin "2") (pinfunction "2_2") (pintype "input"))
      (node (ref "R5") (pin "2") (pinfunction "2_2") (pintype "input"))
    )
    (net (code "18") (name "Net-(Q2-G)") (class "Default")
      (node (ref "Q2") (pin "1") (pinfunction "G_1") (pintype "unspecified"))
      (node (ref "R17") (pin "1") (pinfunction "1_1") (pintype "input"))
      (node (ref "R6") (pin "2") (pinfunction "2_2") (pintype "input"))
    )
    (net (code "19") (name "Net-(Q2-S)") (class "Default")
      (node (ref "Q2") (pin "3") (pinfunction "S_3") (pintype "unspecified"))
      (node (ref "R17") (pin "2") (pinfunction "2_2") (pintype "input"))
      (node (ref "R26") (pin "2") (pinfunction "2_2") (pintype "input"))
      (node (ref "U7") (pin "3") (pinfunction "IN-_3") (pintype "input"))
    )
    (net (code "20") (name "Net-(Q3-G)") (class "Default")
      (node (ref "Q3") (pin "1") (pinfunction "G_1") (pintype "unspecified"))
      (node (ref "R15") (pin "2") (pinfunction "2_2") (pintype "input"))
      (node (ref "R9") (pin "2") (pinfunction "2_2") (pintype "input"))
    )
    (net (code "21") (name "Net-(Q4-G)") (class "Default")
      (node (ref "Q4") (pin "1") (pinfunction "G_1") (pintype "unspecified"))
      (node (ref "R10") (pin "2") (pinfunction "2_2") (pintype "input"))
      (node (ref "R18") (pin "1") (pinfunction "1_1") (pintype "input"))
    )
    (net (code "22") (name "Net-(Q4-S)") (class "Default")
      (node (ref "Q4") (pin "3") (pinfunction "S_3") (pintype "unspecified"))
      (node (ref "R18") (pin "2") (pinfunction "2_2") (pintype "input"))
      (node (ref "R27") (pin "2") (pinfunction "2_2") (pintype "input"))
      (node (ref "U8") (pin "3") (pinfunction "IN-_3") (pintype "input"))
    )
    (net (code "23") (name "Net-(Q5-G)") (class "Default")
      (node (ref "Q5") (pin "1") (pinfunction "G_1") (pintype "unspecified"))
      (node (ref "R16") (pin "2") (pinfunction "2_2") (pintype "input"))
      (node (ref "R7") (pin "2") (pinfunction "2_2") (pintype "input"))
    )
    (net (code "24") (name "Net-(Q6-G)") (class "Default")
      (node (ref "Q6") (pin "1") (pinfunction "G_1") (pintype "unspecified"))
      (node (ref "R19") (pin "1") (pinfunction "1_1") (pintype "input"))
      (node (ref "R8") (pin "2") (pinfunction "2_2") (pintype "input"))
    )
    (net (code "25") (name "Net-(Q6-S)") (class "Default")
      (node (ref "Q6") (pin "3") (pinfunction "S_3") (pintype "unspecified"))
      (node (ref "R19") (pin "2") (pinfunction "2_2") (pintype "input"))
      (node (ref "R28") (pin "2") (pinfunction "2_2") (pintype "input"))
      (node (ref "U9") (pin "3") (pinfunction "IN-_3") (pintype "input"))
    )
    (net (code "26") (name "Net-(R31-Pad1)") (class "Default")
      (node (ref "R31") (pin "1") (pinfunction "1_1") (pintype "input"))
      (node (ref "R32") (pin "1") (pinfunction "1_1") (pintype "input"))
      (node (ref "R33") (pin "1") (pinfunction "1_1") (pintype "input"))
      (node (ref "R34") (pin "2") (pinfunction "2_2") (pintype "input"))
    )
    (net (code "27") (name "Net-(U1-BOOT)") (class "Default")
      (node (ref "C39") (pin "1") (pinfunction "1_1") (pintype "unspecified"))
      (node (ref "U1") (pin "7") (pinfunction "BOOT_7") (pintype "unspecified"))
      (node (ref "U2") (pin "7") (pinfunction "BOOT_7") (pintype "unspecified"))
    )
    (net (code "28") (name "Net-(U1-FB)") (class "Default")
      (node (ref "R1") (pin "1") (pinfunction "1_1") (pintype "input"))
      (node (ref "R2") (pin "1") (pinfunction "1_1") (pintype "input"))
      (node (ref "U1") (pin "5") (pinfunction "FB_5") (pintype "unspecified"))
      (node (ref "U2") (pin "5") (pinfunction "FB_5") (pintype "unspecified"))
    )
    (net (code "29") (name "Net-(U1-PG)") (class "Default")
      (node (ref "U1") (pin "4") (pinfunction "PG_4") (pintype "unspecified"))
      (node (ref "U2") (pin "4") (pinfunction "PG_4") (pintype "unspecified"))
    )
    (net (code "30") (name "Net-(U1-SW)") (class "Default")
      (node (ref "C39") (pin "2") (pinfunction "2_2") (pintype "unspecified"))
      (node (ref "L1") (pin "1") (pinfunction "1_1") (pintype "input"))
      (node (ref "U1") (pin "8") (pinfunction "SW_8") (pintype "unspecified"))
      (node (ref "U2") (pin "8") (pinfunction "SW_8") (pintype "unspecified"))
    )
    (net (code "31") (name "Net-(U1-VCC)") (class "Default")
      (node (ref "C37") (pin "2") (pinfunction "2_2") (pintype "unspecified"))
      (node (ref "U1") (pin "6") (pinfunction "VCC_6") (pintype "unspecified"))
      (node (ref "U2") (pin "6") (pinfunction "VCC_6") (pintype "unspecified"))
    )
    (net (code "32") (name "Net-(U3-BOOT)") (class "Default")
      (node (ref "C38") (pin "1") (pinfunction "1_1") (pintype "unspecified"))
      (node (ref "U3") (pin "7") (pinfunction "BOOT_7") (pintype "unspecified"))
      (node (ref "U4") (pin "7") (pinfunction "BOOT_7") (pintype "unspecified"))
    )
    (net (code "33") (name "Net-(U3-FB)") (class "Default")
      (node (ref "R3") (pin "1") (pinfunction "1_1") (pintype "input"))
      (node (ref "R4") (pin "1") (pinfunction "1_1") (pintype "input"))
      (node (ref "U3") (pin "5") (pinfunction "FB_5") (pintype "unspecified"))
      (node (ref "U4") (pin "5") (pinfunction "FB_5") (pintype "unspecified"))
    )
    (net (code "34") (name "Net-(U3-PG)") (class "Default")
      (node (ref "U3") (pin "4") (pinfunction "PG_4") (pintype "unspecified"))
      (node (ref "U4") (pin "4") (pinfunction "PG_4") (pintype "unspecified"))
    )
    (net (code "35") (name "Net-(U3-SW)") (class "Default")
      (node (ref "C38") (pin "2") (pinfunction "2_2") (pintype "unspecified"))
      (node (ref "L2") (pin "1") (pinfunction "1_1") (pintype "input"))
      (node (ref "U3") (pin "8") (pinfunction "SW_8") (pintype "unspecified"))
      (node (ref "U4") (pin "8") (pinfunction "SW_8") (pintype "unspecified"))
    )
    (net (code "36") (name "Net-(U3-VCC)") (class "Default")
      (node (ref "C36") (pin "2") (pinfunction "2_2") (pintype "unspecified"))
      (node (ref "U3") (pin "6") (pinfunction "VCC_6") (pintype "unspecified"))
      (node (ref "U4") (pin "6") (pinfunction "VCC_6") (pintype "unspecified"))
    )
    (net (code "37") (name "Net-(U5-PA4)") (class "Default")
      (node (ref "R36") (pin "2") (pinfunction "2_2") (pintype "input"))
      (node (ref "U5") (pin "10") (pinfunction "PA4_10") (pintype "unspecified"))
    )
    (net (code "38") (name "Net-(U5-PA7)") (class "Default")
      (node (ref "U5") (pin "13") (pinfunction "PA7_13") (pintype "unspecified"))
      (node (ref "U6") (pin "1") (pinfunction "LIN1_1") (pintype "unspecified"))
    )
    (net (code "39") (name "Net-(U5-PA8)") (class "Default")
      (node (ref "U5") (pin "16") (pinfunction "PA8_16") (pintype "unspecified"))
      (node (ref "U6") (pin "22") (pinfunction "HIN1_22") (pintype "unspecified"))
    )
    (net (code "40") (name "Net-(U5-PA13)") (class "Default")
      (node (ref "H1") (pin "3") (pinfunction "3_3") (pintype "input"))
      (node (ref "U5") (pin "20") (pinfunction "PA13_20") (pintype "unspecified"))
    )
    (net (code "41") (name "Net-(U5-PA14-BOOT0)") (class "Default")
      (node (ref "H1") (pin "4") (pinfunction "4_4") (pintype "input"))
      (node (ref "U5") (pin "21") (pinfunction "PA14-BOOT0_21") (pintype "unspecified"))
    )
    (net (code "42") (name "Net-(U5-PB0)") (class "Default")
      (node (ref "U5") (pin "14") (pinfunction "PB0_14") (pintype "unspecified"))
      (node (ref "U6") (pin "2") (pinfunction "LIN2_2") (pintype "unspecified"))
    )
    (net (code "43") (name "Net-(U5-PB1)") (class "Default")
      (node (ref "U5") (pin "15") (pinfunction "PB1_15") (pintype "unspecified"))
      (node (ref "U6") (pin "3") (pinfunction "LIN3_3") (pintype "unspecified"))
    )
    (net (code "44") (name "Net-(U5-PB3)") (class "Default")
      (node (ref "U5") (pin "23") (pinfunction "PB3_23") (pintype "unspecified"))
      (node (ref "U6") (pin "23") (pinfunction "HIN2_23") (pintype "unspecified"))
    )
    (net (code "45") (name "Net-(U5-PB6)") (class "Default")
      (node (ref "U5") (pin "26") (pinfunction "PB6_26") (pintype "unspecified"))
      (node (ref "U6") (pin "24") (pinfunction "HIN3_24") (pintype "unspecified"))
    )
    (net (code "46") (name "Net-(U5-PF2-NRST)") (class "Default")
      (node (ref "H1") (pin "5") (pinfunction "5_5") (pintype "input"))
      (node (ref "R13") (pin "1") (pinfunction "1_1") (pintype "input"))
      (node (ref "U5") (pin "5") (pinfunction "PF2-NRST_5") (pintype "unspecified"))
    )
    (net (code "47") (name "Net-(U7-OUT)") (class "Default")
      (node (ref "R12") (pin "1") (pinfunction "1_1") (pintype "input"))
      (node (ref "U7") (pin "4") (pinfunction "OUT_4") (pintype "output"))
    )
    (net (code "48") (name "Net-(U8-OUT)") (class "Default")
      (node (ref "R29") (pin "1") (pinfunction "1_1") (pintype "input"))
      (node (ref "U8") (pin "4") (pinfunction "OUT_4") (pintype "output"))
    )
    (net (code "49") (name "Net-(U9-OUT)") (class "Default")
      (node (ref "R30") (pin "1") (pinfunction "1_1") (pintype "input"))
      (node (ref "U9") (pin "4") (pinfunction "OUT_4") (pintype "output"))
    )
    (net (code "50") (name "Net-(U10-OUT)") (class "Default")
      (node (ref "R36") (pin "1") (pinfunction "1_1") (pintype "input"))
      (node (ref "U10") (pin "1") (pinfunction "OUT_1") (pintype "output"))
    )
    (net (code "51") (name "VB1") (class "Default")
      (node (ref "C26") (pin "2") (pinfunction "2_2") (pintype "input"))
      (node (ref "D6") (pin "2") (pinfunction "K_2") (pintype "input"))
      (node (ref "U6") (pin "20") (pinfunction "VB1_20") (pintype "unspecified"))
    )
    (net (code "52") (name "VB2") (class "Default")
      (node (ref "C27") (pin "2") (pinfunction "2_2") (pintype "input"))
      (node (ref "D7") (pin "2") (pinfunction "K_2") (pintype "input"))
      (node (ref "U6") (pin "17") (pinfunction "VB2_17") (pintype "unspecified"))
    )
    (net (code "53") (name "VB3") (class "Default")
      (node (ref "C28") (pin "2") (pinfunction "2_2") (pintype "input"))
      (node (ref "D8") (pin "2") (pinfunction "K_2") (pintype "input"))
      (node (ref "U6") (pin "14") (pinfunction "VB3_14") (pintype "unspecified"))
    )
    (net (code "54") (name "VBAT+") (class "Default")
      (node (ref "Q1") (pin "2") (pinfunction "D_2") (pintype "unspecified"))
      (node (ref "Q3") (pin "2") (pinfunction "D_2") (pintype "unspecified"))
      (node (ref "Q5") (pin "2") (pinfunction "D_2") (pintype "unspecified"))
    )
    (net (code "55") (name "VREF") (class "Default")
      (node (ref "R34") (pin "1") (pinfunction "1_1") (pintype "input"))
      (node (ref "R35") (pin "2") (pinfunction "2_2") (pintype "input"))
      (node (ref "U10") (pin "4") (pinfunction "IN-_4") (pintype "input"))
      (node (ref "U5") (pin "27") (pinfunction "PB7_27") (pintype "unspecified"))
      (node (ref "U5") (pin "8") (pinfunction "PA2_8") (pintype "unspecified"))
    )
    (net (code "56") (name "VS1") (class "Default")
      (node (ref "C26") (pin "1") (pinfunction "1_1") (pintype "input"))
      (node (ref "Q1") (pin "3") (pinfunction "S_3") (pintype "unspecified"))
      (node (ref "Q2") (pin "2") (pinfunction "D_2") (pintype "unspecified"))
      (node (ref "R14") (pin "1") (pinfunction "1_1") (pintype "input"))
      (node (ref "R20") (pin "2") (pinfunction "2_2") (pintype "input"))
      (node (ref "R31") (pin "2") (pinfunction "2_2") (pintype "input"))
      (node (ref "U6") (pin "18") (pinfunction "VS1_18") (pintype "unspecified"))
    )
    (net (code "57") (name "VS2") (class "Default")
      (node (ref "C27") (pin "1") (pinfunction "1_1") (pintype "input"))
      (node (ref "Q3") (pin "3") (pinfunction "S_3") (pintype "unspecified"))
      (node (ref "Q4") (pin "2") (pinfunction "D_2") (pintype "unspecified"))
      (node (ref "R15") (pin "1") (pinfunction "1_1") (pintype "input"))
      (node (ref "R22") (pin "2") (pinfunction "2_2") (pintype "input"))
      (node (ref "R32") (pin "2") (pinfunction "2_2") (pintype "input"))
      (node (ref "U6") (pin "15") (pinfunction "VS2_15") (pintype "unspecified"))
    )
    (net (code "58") (name "VS3") (class "Default")
      (node (ref "C28") (pin "1") (pinfunction "1_1") (pintype "input"))
      (node (ref "Q5") (pin "3") (pinfunction "S_3") (pintype "unspecified"))
      (node (ref "Q6") (pin "2") (pinfunction "D_2") (pintype "unspecified"))
      (node (ref "R16") (pin "1") (pinfunction "1_1") (pintype "input"))
      (node (ref "R24") (pin "2") (pinfunction "2_2") (pintype "input"))
      (node (ref "R33") (pin "2") (pinfunction "2_2") (pintype "input"))
      (node (ref "U6") (pin "12") (pinfunction "VS3_12") (pintype "unspecified"))
    )
    (net (code "59") (name "unconnected-(U5-PA11[PA9]-Pad18)") (class "Default")
      (node (ref "U5") (pin "18") (pinfunction "PA11[PA9]_18") (pintype "unspecified"))
    )
    (net (code "60") (name "unconnected-(U5-PA12[PA10]-Pad19)") (class "Default")
      (node (ref "U5") (pin "19") (pinfunction "PA12[PA10]_19") (pintype "unspecified"))
    )
    (net (code "61") (name "unconnected-(U5-PA15-Pad22)") (class "Default")
      (node (ref "U5") (pin "22") (pinfunction "PA15_22") (pintype "unspecified"))
    )
    (net (code "62") (name "unconnected-(U5-PB4-Pad24)") (class "Default")
      (node (ref "U5") (pin "24") (pinfunction "PB4_24") (pintype "unspecified"))
    )
    (net (code "63") (name "unconnected-(U5-PB5-Pad25)") (class "Default")
      (node (ref "U5") (pin "25") (pinfunction "PB5_25") (pintype "unspecified"))
    )
    (net (code "64") (name "unconnected-(U5-PB8-Pad28)") (class "Default")
      (node (ref "U5") (pin "28") (pinfunction "PB8_28") (pintype "unspecified"))
    )
    (net (code "65") (name "unconnected-(U5-PC6-Pad17)") (class "Default")
      (node (ref "U5") (pin "17") (pinfunction "PC6_17") (pintype "unspecified"))
    )
    (net (code "66") (name "unconnected-(U5-PC14-OSC32_IN-Pad1)") (class "Default")
      (node (ref "U5") (pin "1") (pinfunction "PC14-OSC32_IN_1") (pintype "unspecified"))
    )
    (net (code "67") (name "unconnected-(U5-PC15-OSC32_OUT-Pad2)") (class "Default")
      (node (ref "U5") (pin "2") (pinfunction "PC15-OSC32_OUT_2") (pintype "unspecified"))
    )
    (net (code "68") (name "unconnected-(U6-NC-Pad5)") (class "Default")
      (node (ref "U6") (pin "5") (pinfunction "NC_5") (pintype "unspecified"))
    )
    (net (code "69") (name "unconnected-(U6-NC-Pad7)") (class "Default")
      (node (ref "U6") (pin "7") (pinfunction "NC_7") (pintype "unspecified"))
    )
    (net (code "70") (name "unconnected-(U6-NC-Pad8)") (class "Default")
      (node (ref "U6") (pin "8") (pinfunction "NC_8") (pintype "unspecified"))
    )
    (net (code "71") (name "unconnected-(U6-NC-Pad21)") (class "Default")
      (node (ref "U6") (pin "21") (pinfunction "NC_21") (pintype "unspecified"))
    )
  )
)
